# LKS_EVB_MCU081_V2_0.net
KiCad netlist of a schematic drawn in Altium Designer
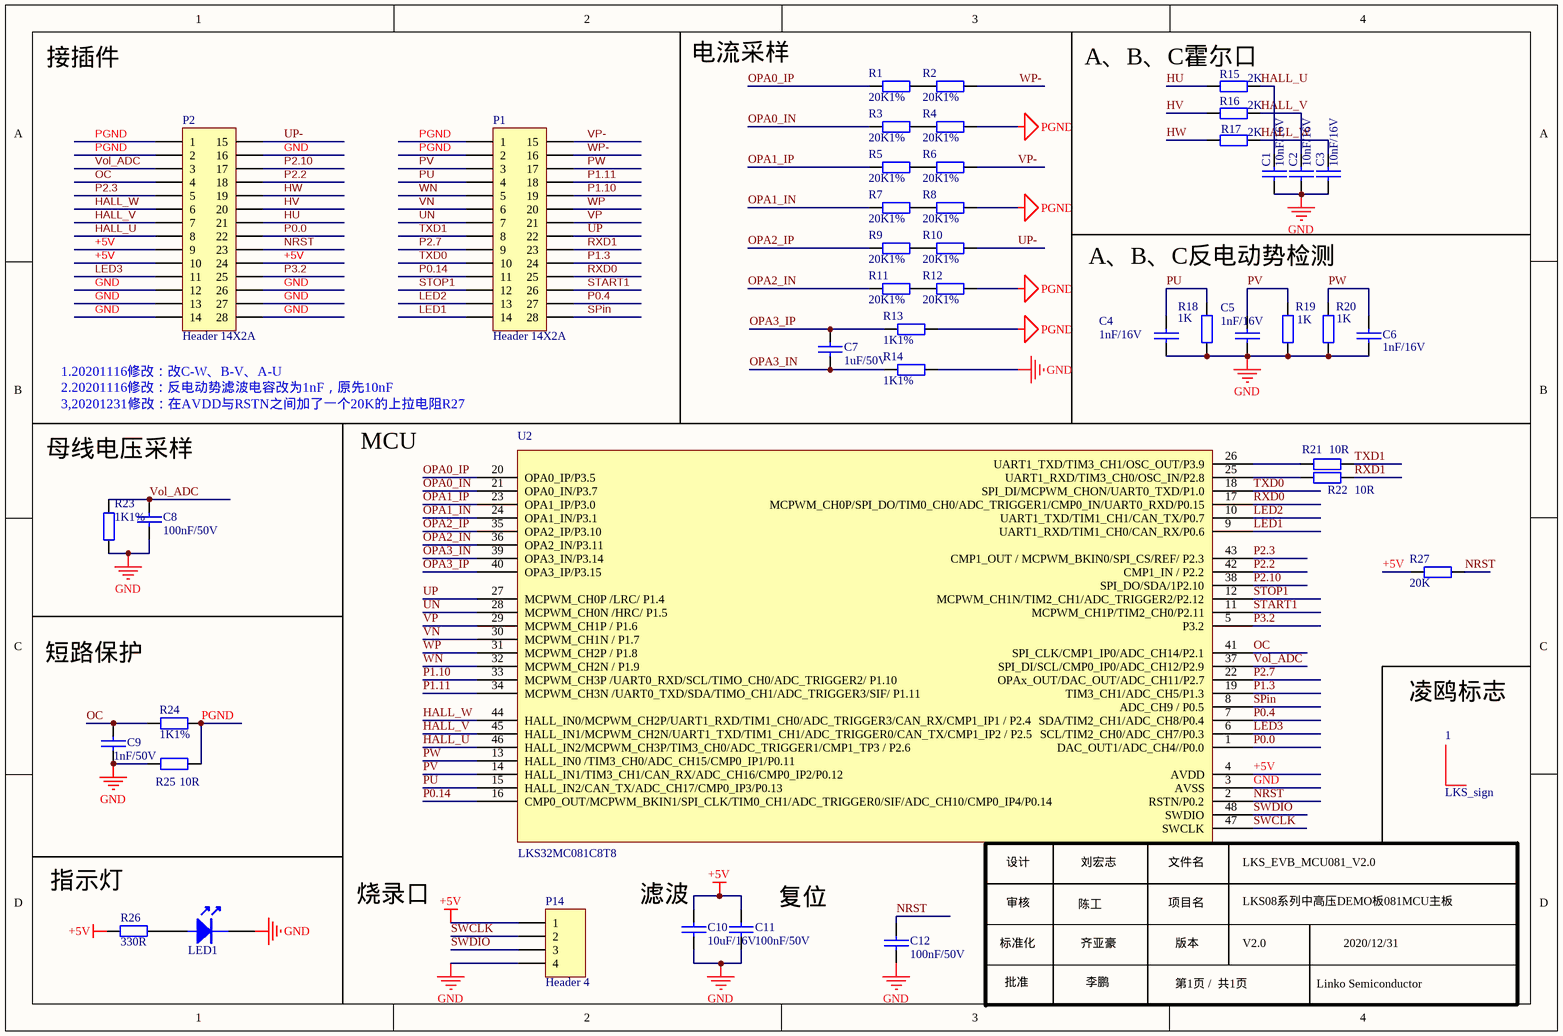
[diagram p0: LKS_EVB_MCU081_V2.0.SchDoc]

(export (version "E")
  (design (tool "Eeschema 10.0.6"))
  (components
    (comp (ref "1")
      (value "LKS_sign")
      (footprint "LKS_LOGO2")
      (libsource (lib "linko sch library") (part "LKS_sign"))
    )
    (comp (ref "C1")
      (value "10nF/16V")
      (footprint "0603C")
      (description "Capacitor")
      (libsource (lib "*") (part "CAP"))
    )
    (comp (ref "C2")
      (value "10nF/16V")
      (footprint "0603C")
      (description "Capacitor")
      (libsource (lib "*") (part "CAP"))
    )
    (comp (ref "C3")
      (value "10nF/16V")
      (footprint "0603C")
      (description "Capacitor")
      (libsource (lib "*") (part "CAP"))
    )
    (comp (ref "C4")
      (value "1nF/16V")
      (footprint "0603C")
      (description "Capacitor")
      (libsource (lib "*") (part "CAP"))
    )
    (comp (ref "C5")
      (value "1nF/16V")
      (footprint "0603C")
      (description "Capacitor")
      (libsource (lib "*") (part "CAP"))
    )
    (comp (ref "C6")
      (value "1nF/16V")
      (footprint "0603C")
      (description "Capacitor")
      (libsource (lib "*") (part "CAP"))
    )
    (comp (ref "C7")
      (value "1uF/50V")
      (footprint "0603C")
      (description "Capacitor")
      (libsource (lib "*") (part "C"))
    )
    (comp (ref "C8")
      (value "100nF/50V")
      (footprint "0603C")
      (description "Capacitor")
      (libsource (lib "*") (part "C"))
    )
    (comp (ref "C9")
      (value "1nF/50V")
      (footprint "0603C")
      (description "Capacitor")
      (libsource (lib "*") (part "C"))
    )
    (comp (ref "C10")
      (value "10uF/16V")
      (footprint "0603C")
      (description "Capacitor")
      (libsource (lib "*") (part "C"))
    )
    (comp (ref "C11")
      (value "100nF/50V")
      (footprint "0603C")
      (description "Capacitor")
      (libsource (lib "*") (part "C"))
    )
    (comp (ref "C12")
      (value "100nF/50V")
      (footprint "0603C")
      (description "Capacitor")
      (libsource (lib "*") (part "C"))
    )
    (comp (ref "LED1")
      (value "LED")
      (footprint "LED 0603R")
      (description "LED_Light")
      (libsource (lib "LINKO_V1.0") (part "LED"))
    )
    (comp (ref "P1")
      (value "Header 14X2A")
      (footprint "HDR2X14_CEN")
      (description "Header, 14-Pin, Dual row")
      (fields (field (name "PUBLISHER") "Altium Limited"))
      (libsource (lib "Miscellaneous Connectors") (part "Header 14X2A"))
    )
    (comp (ref "P2")
      (value "Header 14X2A")
      (footprint "HDR2X14_CEN")
      (description "Header, 14-Pin, Dual row")
      (fields (field (name "PUBLISHER") "Altium Limited"))
      (libsource (lib "Miscellaneous Connectors") (part "Header 14X2A"))
    )
    (comp (ref "P14")
      (value "Header 4")
      (footprint "HDR1X4")
      (description "Header, 4-Pin")
      (fields (field (name "PUBLISHER") "Altium Limited"))
      (libsource (lib "Miscellaneous Connectors") (part "Header 4"))
    )
    (comp (ref "R1")
      (value "20K1%")
      (footprint "0603R")
      (description "Resistor")
      (fields (field (name "PUBLISHER") "Altium Limited"))
      (libsource (lib "LINKO_V1.0") (part "Res"))
    )
    (comp (ref "R2")
      (value "20K1%")
      (footprint "0603R")
      (description "Resistor")
      (fields (field (name "PUBLISHER") "Altium Limited"))
      (libsource (lib "LINKO_V1.0") (part "Res"))
    )
    (comp (ref "R3")
      (value "20K1%")
      (footprint "0603R")
      (description "Resistor")
      (fields (field (name "PUBLISHER") "Altium Limited"))
      (libsource (lib "LINKO_V1.0") (part "Res"))
    )
    (comp (ref "R4")
      (value "20K1%")
      (footprint "0603R")
      (description "Resistor")
      (fields (field (name "PUBLISHER") "Altium Limited"))
      (libsource (lib "LINKO_V1.0") (part "Res"))
    )
    (comp (ref "R5")
      (value "20K1%")
      (footprint "0603R")
      (description "Resistor")
      (fields (field (name "PUBLISHER") "Altium Limited"))
      (libsource (lib "LINKO_V1.0") (part "Res"))
    )
    (comp (ref "R6")
      (value "20K1%")
      (footprint "0603R")
      (description "Resistor")
      (fields (field (name "PUBLISHER") "Altium Limited"))
      (libsource (lib "LINKO_V1.0") (part "Res"))
    )
    (comp (ref "R7")
      (value "20K1%")
      (footprint "0603R")
      (description "Resistor")
      (fields (field (name "PUBLISHER") "Altium Limited"))
      (libsource (lib "LINKO_V1.0") (part "Res"))
    )
    (comp (ref "R8")
      (value "20K1%")
      (footprint "0603R")
      (description "Resistor")
      (fields (field (name "PUBLISHER") "Altium Limited"))
      (libsource (lib "LINKO_V1.0") (part "Res"))
    )
    (comp (ref "R9")
      (value "20K1%")
      (footprint "0603R")
      (description "Resistor")
      (fields (field (name "PUBLISHER") "Altium Limited"))
      (libsource (lib "LINKO_V1.0") (part "Res"))
    )
    (comp (ref "R10")
      (value "20K1%")
      (footprint "0603R")
      (description "Resistor")
      (fields (field (name "PUBLISHER") "Altium Limited"))
      (libsource (lib "LINKO_V1.0") (part "Res"))
    )
    (comp (ref "R11")
      (value "20K1%")
      (footprint "0603R")
      (description "Resistor")
      (fields (field (name "PUBLISHER") "Altium Limited"))
      (libsource (lib "LINKO_V1.0") (part "Res"))
    )
    (comp (ref "R12")
      (value "20K1%")
      (footprint "0603R")
      (description "Resistor")
      (fields (field (name "PUBLISHER") "Altium Limited"))
      (libsource (lib "LINKO_V1.0") (part "Res"))
    )
    (comp (ref "R13")
      (value "1K1%")
      (footprint "0603R")
      (description "Resistor")
      (fields (field (name "PUBLISHER") "Altium Limited"))
      (libsource (lib "LINKO_V1.0") (part "Res"))
    )
    (comp (ref "R14")
      (value "1K1%")
      (footprint "0603R")
      (description "Resistor")
      (fields (field (name "PUBLISHER") "Altium Limited"))
      (libsource (lib "LINKO_V1.0") (part "Res"))
    )
    (comp (ref "R15")
      (value "2K")
      (footprint "0603R")
      (description "Resistor")
      (fields (field (name "PUBLISHER") "Altium Limited"))
      (libsource (lib "") (part "Res_2"))
    )
    (comp (ref "R16")
      (value "2K")
      (footprint "0603R")
      (description "Resistor")
      (fields (field (name "PUBLISHER") "Altium Limited"))
      (libsource (lib "") (part "Res_2"))
    )
    (comp (ref "R17")
      (value "2K")
      (footprint "0603R")
      (description "Resistor")
      (fields (field (name "PUBLISHER") "Altium Limited"))
      (libsource (lib "") (part "Res_2"))
    )
    (comp (ref "R18")
      (value "1K")
      (footprint "0603R")
      (description "Resistor")
      (fields (field (name "PUBLISHER") "Altium Limited"))
      (libsource (lib "LINKO_V1.0") (part "Res"))
    )
    (comp (ref "R19")
      (value "1K")
      (footprint "0603R")
      (description "Resistor")
      (fields (field (name "PUBLISHER") "Altium Limited"))
      (libsource (lib "LINKO_V1.0") (part "Res"))
    )
    (comp (ref "R20")
      (value "1K")
      (footprint "0603R")
      (description "Resistor")
      (fields (field (name "PUBLISHER") "Altium Limited"))
      (libsource (lib "LINKO_V1.0") (part "Res"))
    )
    (comp (ref "R21")
      (value "10R")
      (footprint "0603R")
      (description "Resistor")
      (fields (field (name "PUBLISHER") "Altium Limited"))
      (libsource (lib "") (part "Res_3"))
    )
    (comp (ref "R22")
      (value "10R")
      (footprint "0603R")
      (description "Resistor")
      (fields (field (name "PUBLISHER") "Altium Limited"))
      (libsource (lib "") (part "Res_1"))
    )
    (comp (ref "R23")
      (value "1K1%")
      (footprint "0603R")
      (description "Resistor")
      (fields (field (name "PUBLISHER") "Altium Limited"))
      (libsource (lib "") (part "Res_1"))
    )
    (comp (ref "R24")
      (value "1K1%")
      (footprint "0603R")
      (description "Resistor")
      (fields (field (name "PUBLISHER") "Altium Limited"))
      (libsource (lib "") (part "Res_2"))
    )
    (comp (ref "R25")
      (value "10R")
      (footprint "0603R")
      (description "Resistor")
      (fields (field (name "PUBLISHER") "Altium Limited"))
      (libsource (lib "LINKO_V1.0") (part "Res"))
    )
    (comp (ref "R26")
      (value "330R")
      (footprint "0603R")
      (description "Resistor")
      (fields (field (name "PUBLISHER") "Altium Limited"))
      (libsource (lib "") (part "Res_1"))
    )
    (comp (ref "R27")
      (value "20K")
      (footprint "0603R")
      (description "Resistor")
      (fields (field (name "PUBLISHER") "Altium Limited"))
      (libsource (lib "LINKO_V1.0") (part "Res"))
    )
    (comp (ref "U2")
      (value "LKS32MC081C8T8")
      (footprint "LINKO-081")
      (description "芯片")
      (libsource (lib "LINKO_V1.0") (part "LKS081C8T8"))
    )
  )
  (nets
    (net (code "1") (name "+5V") (class "Default")
      (node (ref "C10") (pin "2") (pinfunction "2_2") (pintype "passive"))
      (node (ref "C11") (pin "2") (pinfunction "2_2") (pintype "passive"))
      (node (ref "P14") (pin "1") (pinfunction "1_1") (pintype "passive"))
      (node (ref "P2") (pin "10") (pinfunction "10_10") (pintype "passive"))
      (node (ref "P2") (pin "24") (pinfunction "24_24") (pintype "passive"))
      (node (ref "P2") (pin "9") (pinfunction "9_9") (pintype "passive"))
      (node (ref "R26") (pin "1") (pinfunction "1_1") (pintype "passive"))
      (node (ref "R27") (pin "2") (pinfunction "2_2") (pintype "passive"))
      (node (ref "U2") (pin "4") (pinfunction "AVDD_4") (pintype "passive"))
    )
    (net (code "2") (name "/HALL_U") (class "Default")
      (node (ref "C1") (pin "1") (pinfunction "1_1") (pintype "passive"))
      (node (ref "P2") (pin "8") (pinfunction "8_8") (pintype "passive"))
      (node (ref "R15") (pin "2") (pinfunction "2_2") (pintype "passive"))
      (node (ref "U2") (pin "46") (pinfunction "HALL_IN2/MCPWM_CH3P/TIM3_CH0/ADC_TRIGGER1/CMP1_TP3_/_P2.6_46") (pintype "passive"))
    )
    (net (code "3") (name "/HALL_V") (class "Default")
      (node (ref "C2") (pin "1") (pinfunction "1_1") (pintype "passive"))
      (node (ref "P2") (pin "7") (pinfunction "7_7") (pintype "passive"))
      (node (ref "R16") (pin "2") (pinfunction "2_2") (pintype "passive"))
      (node (ref "U2") (pin "45") (pinfunction "HALL_IN1/MCPWM_CH2N/UART1_TXD/TIM1_CH1/ADC_TRIGGER0/CAN_TX/CMP1_IP2_/_P2.5_45") (pintype "passive"))
    )
    (net (code "4") (name "/HALL_W") (class "Default")
      (node (ref "C3") (pin "1") (pinfunction "1_1") (pintype "passive"))
      (node (ref "P2") (pin "6") (pinfunction "6_6") (pintype "passive"))
      (node (ref "R17") (pin "2") (pinfunction "2_2") (pintype "passive"))
      (node (ref "U2") (pin "44") (pinfunction "HALL_IN0/MCPWM_CH2P/UART1_RXD/TIM1_CH0/ADC_TRIGGER3/CAN_RX/CMP1_IP1_/_P2.4_44") (pintype "passive"))
    )
    (net (code "5") (name "/HU") (class "Default")
      (node (ref "P2") (pin "21") (pinfunction "21_21") (pintype "passive"))
      (node (ref "R15") (pin "1") (pinfunction "1_1") (pintype "passive"))
    )
    (net (code "6") (name "/HV") (class "Default")
      (node (ref "P2") (pin "20") (pinfunction "20_20") (pintype "passive"))
      (node (ref "R16") (pin "1") (pinfunction "1_1") (pintype "passive"))
    )
    (net (code "7") (name "/HW") (class "Default")
      (node (ref "P2") (pin "19") (pinfunction "19_19") (pintype "passive"))
      (node (ref "R17") (pin "1") (pinfunction "1_1") (pintype "passive"))
    )
    (net (code "8") (name "/LED1") (class "Default")
      (node (ref "P1") (pin "14") (pinfunction "14_14") (pintype "passive"))
      (node (ref "U2") (pin "9") (pinfunction "UART1_RXD/TIM1_CH0/CAN_RX/P0.6_9") (pintype "passive"))
    )
    (net (code "9") (name "/LED2") (class "Default")
      (node (ref "P1") (pin "13") (pinfunction "13_13") (pintype "passive"))
      (node (ref "U2") (pin "10") (pinfunction "UART1_TXD/TIM1_CH1/CAN_TX/P0.7_10") (pintype "passive"))
    )
    (net (code "10") (name "/LED3") (class "Default")
      (node (ref "P2") (pin "11") (pinfunction "11_11") (pintype "passive"))
      (node (ref "U2") (pin "6") (pinfunction "SCL/TIM2_CH0/ADC_CH7/P0.3_6") (pintype "passive"))
    )
    (net (code "11") (name "/NRST") (class "Default")
      (node (ref "C12") (pin "1") (pinfunction "1_1") (pintype "passive"))
      (node (ref "P2") (pin "23") (pinfunction "23_23") (pintype "passive"))
      (node (ref "R27") (pin "1") (pinfunction "1_1") (pintype "passive"))
      (node (ref "U2") (pin "2") (pinfunction "RSTN/P0.2_2") (pintype "passive"))
    )
    (net (code "12") (name "/OC") (class "Default")
      (node (ref "C9") (pin "2") (pinfunction "2_2") (pintype "passive"))
      (node (ref "P2") (pin "4") (pinfunction "4_4") (pintype "passive"))
      (node (ref "R24") (pin "1") (pinfunction "1_1") (pintype "passive"))
      (node (ref "U2") (pin "41") (pinfunction "SPI_CLK/CMP1_IP0/ADC_CH14/P2.1_41") (pintype "passive"))
    )
    (net (code "13") (name "/OPA0_IN") (class "Default")
      (node (ref "R3") (pin "2") (pinfunction "2_2") (pintype "passive"))
      (node (ref "U2") (pin "21") (pinfunction "OPA0_IN/P3.7_21") (pintype "passive"))
    )
    (net (code "14") (name "/OPA0_IP") (class "Default")
      (node (ref "R1") (pin "2") (pinfunction "2_2") (pintype "passive"))
      (node (ref "U2") (pin "20") (pinfunction "OPA0_IP/P3.5_20") (pintype "passive"))
    )
    (net (code "15") (name "/OPA1_IN") (class "Default")
      (node (ref "R7") (pin "2") (pinfunction "2_2") (pintype "passive"))
      (node (ref "U2") (pin "24") (pinfunction "OPA1_IN/P3.1_24") (pintype "passive"))
    )
    (net (code "16") (name "/OPA1_IP") (class "Default")
      (node (ref "R5") (pin "2") (pinfunction "2_2") (pintype "passive"))
      (node (ref "U2") (pin "23") (pinfunction "OPA1_IP/P3.0_23") (pintype "passive"))
    )
    (net (code "17") (name "/OPA2_IN") (class "Default")
      (node (ref "R11") (pin "2") (pinfunction "2_2") (pintype "passive"))
      (node (ref "U2") (pin "36") (pinfunction "OPA2_IN/P3.11_36") (pintype "passive"))
    )
    (net (code "18") (name "/OPA2_IP") (class "Default")
      (node (ref "R9") (pin "2") (pinfunction "2_2") (pintype "passive"))
      (node (ref "U2") (pin "35") (pinfunction "OPA2_IP/P3.10_35") (pintype "passive"))
    )
    (net (code "19") (name "/OPA3_IN") (class "Default")
      (node (ref "C7") (pin "2") (pinfunction "2_2") (pintype "passive"))
      (node (ref "R14") (pin "2") (pinfunction "2_2") (pintype "passive"))
      (node (ref "U2") (pin "39") (pinfunction "OPA3_IN/P3.14_39") (pintype "passive"))
    )
    (net (code "20") (name "/OPA3_IP") (class "Default")
      (node (ref "C7") (pin "1") (pinfunction "1_1") (pintype "passive"))
      (node (ref "R13") (pin "2") (pinfunction "2_2") (pintype "passive"))
      (node (ref "U2") (pin "40") (pinfunction "OPA3_IP/P3.15_40") (pintype "passive"))
    )
    (net (code "21") (name "/P0.0") (class "Default")
      (node (ref "P2") (pin "22") (pinfunction "22_22") (pintype "passive"))
      (node (ref "U2") (pin "1") (pinfunction "DAC_OUT1/ADC_CH4//P0.0_1") (pintype "passive"))
    )
    (net (code "22") (name "/P0.4") (class "Default")
      (node (ref "P1") (pin "27") (pinfunction "27_27") (pintype "passive"))
      (node (ref "U2") (pin "7") (pinfunction "SDA/TIM2_CH1/ADC_CH8/P0.4_7") (pintype "passive"))
    )
    (net (code "23") (name "/P0.14") (class "Default")
      (node (ref "P1") (pin "11") (pinfunction "11_11") (pintype "passive"))
      (node (ref "U2") (pin "16") (pinfunction "CMP0_OUT/MCPWM_BKIN1/SPI_CLK/TIM0_CH1/ADC_TRIGGER0/SIF/ADC_CH10/CMP0_IP4/P0.14_16") (pintype "passive"))
    )
    (net (code "24") (name "/P1.3") (class "Default")
      (node (ref "P1") (pin "24") (pinfunction "24_24") (pintype "passive"))
      (node (ref "U2") (pin "19") (pinfunction "TIM3_CH1/ADC_CH5/P1.3_19") (pintype "passive"))
    )
    (net (code "25") (name "/P1.10") (class "Default")
      (node (ref "P1") (pin "19") (pinfunction "19_19") (pintype "passive"))
      (node (ref "U2") (pin "33") (pinfunction "MCPWM_CH3P_/UART0_RXD/SCL/TIMO_CH0/ADC_TRIGGER2/_P1.10_33") (pintype "passive"))
    )
    (net (code "26") (name "/P1.11") (class "Default")
      (node (ref "P1") (pin "18") (pinfunction "18_18") (pintype "passive"))
      (node (ref "U2") (pin "34") (pinfunction "MCPWM_CH3N_/UART0_TXD/SDA/TIMO_CH1/ADC_TRIGGER3/SIF/_P1.11_34") (pintype "passive"))
    )
    (net (code "27") (name "/P2.2") (class "Default")
      (node (ref "P2") (pin "18") (pinfunction "18_18") (pintype "passive"))
      (node (ref "U2") (pin "42") (pinfunction "CMP1_IN_/_P2.2_42") (pintype "passive"))
    )
    (net (code "28") (name "/P2.3") (class "Default")
      (node (ref "P2") (pin "5") (pinfunction "5_5") (pintype "passive"))
      (node (ref "U2") (pin "43") (pinfunction "CMP1_OUT_/_MCPWM_BKIN0/SPI_CS/REF/_P2.3_43") (pintype "passive"))
    )
    (net (code "29") (name "/P2.7") (class "Default")
      (node (ref "P1") (pin "9") (pinfunction "9_9") (pintype "passive"))
      (node (ref "U2") (pin "22") (pinfunction "OPAx_OUT/DAC_OUT/ADC_CH11/P2.7_22") (pintype "passive"))
    )
    (net (code "30") (name "/P2.10") (class "Default")
      (node (ref "P2") (pin "17") (pinfunction "17_17") (pintype "passive"))
      (node (ref "U2") (pin "38") (pinfunction "SPI_DO/SDA/1P2.10_38") (pintype "passive"))
    )
    (net (code "31") (name "/P3.2") (class "Default")
      (node (ref "P2") (pin "25") (pinfunction "25_25") (pintype "passive"))
      (node (ref "U2") (pin "5") (pinfunction "P3.2_5") (pintype "passive"))
    )
    (net (code "32") (name "/PU") (class "Default")
      (node (ref "C4") (pin "1") (pinfunction "1_1") (pintype "passive"))
      (node (ref "P1") (pin "4") (pinfunction "4_4") (pintype "passive"))
      (node (ref "R18") (pin "1") (pinfunction "1_1") (pintype "passive"))
      (node (ref "U2") (pin "15") (pinfunction "HALL_IN2/CAN_TX/ADC_CH17/CMP0_IP3/P0.13_15") (pintype "passive"))
    )
    (net (code "33") (name "/PV") (class "Default")
      (node (ref "C5") (pin "1") (pinfunction "1_1") (pintype "passive"))
      (node (ref "P1") (pin "3") (pinfunction "3_3") (pintype "passive"))
      (node (ref "R19") (pin "1") (pinfunction "1_1") (pintype "passive"))
      (node (ref "U2") (pin "14") (pinfunction "HALL_IN1/TIM3_CH1/CAN_RX/ADC_CH16/CMP0_IP2/P0.12_14") (pintype "passive"))
    )
    (net (code "34") (name "/PW") (class "Default")
      (node (ref "C6") (pin "1") (pinfunction "1_1") (pintype "passive"))
      (node (ref "P1") (pin "17") (pinfunction "17_17") (pintype "passive"))
      (node (ref "R20") (pin "1") (pinfunction "1_1") (pintype "passive"))
      (node (ref "U2") (pin "13") (pinfunction "HALL_IN0_/TIM3_CH0/ADC_CH15/CMP0_IP1/P0.11_13") (pintype "passive"))
    )
    (net (code "35") (name "/RXD0") (class "Default")
      (node (ref "P1") (pin "25") (pinfunction "25_25") (pintype "passive"))
      (node (ref "U2") (pin "17") (pinfunction "MCPWM_CH0P/SPI_DO/TIM0_CH0/ADC_TRIGGER1/CMP0_IN/UART0_RXD/P0.15_17") (pintype "passive"))
    )
    (net (code "36") (name "/RXD1") (class "Default")
      (node (ref "P1") (pin "23") (pinfunction "23_23") (pintype "passive"))
      (node (ref "R22") (pin "2") (pinfunction "2_2") (pintype "passive"))
    )
    (net (code "37") (name "/SPin") (class "Default")
      (node (ref "P1") (pin "28") (pinfunction "28_28") (pintype "passive"))
      (node (ref "U2") (pin "8") (pinfunction "ADC_CH9_/_P0.5_8") (pintype "passive"))
    )
    (net (code "38") (name "/START1") (class "Default")
      (node (ref "P1") (pin "26") (pinfunction "26_26") (pintype "passive"))
      (node (ref "U2") (pin "11") (pinfunction "MCPWM_CH1P/TIM2_CH0/P2.11_11") (pintype "passive"))
    )
    (net (code "39") (name "/STOP1") (class "Default")
      (node (ref "P1") (pin "12") (pinfunction "12_12") (pintype "passive"))
      (node (ref "U2") (pin "12") (pinfunction "MCPWM_CH1N/TIM2_CH1/ADC_TRIGGER2/P2.12_12") (pintype "passive"))
    )
    (net (code "40") (name "/SWCLK") (class "Default")
      (node (ref "P14") (pin "2") (pinfunction "2_2") (pintype "passive"))
      (node (ref "U2") (pin "47") (pinfunction "SWCLK_47") (pintype "passive"))
    )
    (net (code "41") (name "/SWDIO") (class "Default")
      (node (ref "P14") (pin "3") (pinfunction "3_3") (pintype "passive"))
      (node (ref "U2") (pin "48") (pinfunction "SWDIO_48") (pintype "passive"))
    )
    (net (code "42") (name "/TXD0") (class "Default")
      (node (ref "P1") (pin "10") (pinfunction "10_10") (pintype "passive"))
      (node (ref "U2") (pin "18") (pinfunction "SPI_DI/MCPWM_CHON/UART0_TXD/P1.0_18") (pintype "passive"))
    )
    (net (code "43") (name "/TXD1") (class "Default")
      (node (ref "P1") (pin "8") (pinfunction "8_8") (pintype "passive"))
      (node (ref "R21") (pin "1") (pinfunction "1_1") (pintype "passive"))
    )
    (net (code "44") (name "/UN") (class "Default")
      (node (ref "P1") (pin "7") (pinfunction "7_7") (pintype "passive"))
      (node (ref "U2") (pin "28") (pinfunction "MCPWM_CH0N_/HRC/_P1.5_28") (pintype "passive"))
    )
    (net (code "45") (name "/UP") (class "Default")
      (node (ref "P1") (pin "22") (pinfunction "22_22") (pintype "passive"))
      (node (ref "U2") (pin "27") (pinfunction "MCPWM_CH0P_/LRC/_P1.4_27") (pintype "passive"))
    )
    (net (code "46") (name "/UP-") (class "Default")
      (node (ref "P2") (pin "15") (pinfunction "15_15") (pintype "passive"))
      (node (ref "R10") (pin "1") (pinfunction "1_1") (pintype "passive"))
    )
    (net (code "47") (name "/VN") (class "Default")
      (node (ref "P1") (pin "6") (pinfunction "6_6") (pintype "passive"))
      (node (ref "U2") (pin "30") (pinfunction "MCPWM_CH1N_/_P1.7_30") (pintype "passive"))
    )
    (net (code "48") (name "/VP") (class "Default")
      (node (ref "P1") (pin "21") (pinfunction "21_21") (pintype "passive"))
      (node (ref "U2") (pin "29") (pinfunction "MCPWM_CH1P_/_P1.6_29") (pintype "passive"))
    )
    (net (code "49") (name "/VP-") (class "Default")
      (node (ref "P1") (pin "15") (pinfunction "15_15") (pintype "passive"))
      (node (ref "R6") (pin "1") (pinfunction "1_1") (pintype "passive"))
    )
    (net (code "50") (name "/Vol_ADC") (class "Default")
      (node (ref "C8") (pin "2") (pinfunction "2_2") (pintype "passive"))
      (node (ref "P2") (pin "3") (pinfunction "3_3") (pintype "passive"))
      (node (ref "R23") (pin "2") (pinfunction "2_2") (pintype "passive"))
      (node (ref "U2") (pin "37") (pinfunction "SPI_DI/SCL/CMP0_IP0/ADC_CH12/P2.9_37") (pintype "passive"))
    )
    (net (code "51") (name "/WN") (class "Default")
      (node (ref "P1") (pin "5") (pinfunction "5_5") (pintype "passive"))
      (node (ref "U2") (pin "32") (pinfunction "MCPWM_CH2N_/_P1.9_32") (pintype "passive"))
    )
    (net (code "52") (name "/WP") (class "Default")
      (node (ref "P1") (pin "20") (pinfunction "20_20") (pintype "passive"))
      (node (ref "U2") (pin "31") (pinfunction "MCPWM_CH2P_/_P1.8_31") (pintype "passive"))
    )
    (net (code "53") (name "/WP-") (class "Default")
      (node (ref "P1") (pin "16") (pinfunction "16_16") (pintype "passive"))
      (node (ref "R2") (pin "1") (pinfunction "1_1") (pintype "passive"))
    )
    (net (code "54") (name "GND") (class "Default")
      (node (ref "C1") (pin "2") (pinfunction "2_2") (pintype "passive"))
      (node (ref "C10") (pin "1") (pinfunction "1_1") (pintype "passive"))
      (node (ref "C11") (pin "1") (pinfunction "1_1") (pintype "passive"))
      (node (ref "C12") (pin "2") (pinfunction "2_2") (pintype "passive"))
      (node (ref "C2") (pin "2") (pinfunction "2_2") (pintype "passive"))
      (node (ref "C3") (pin "2") (pinfunction "2_2") (pintype "passive"))
      (node (ref "C4") (pin "2") (pinfunction "2_2") (pintype "passive"))
      (node (ref "C5") (pin "2") (pinfunction "2_2") (pintype "passive"))
      (node (ref "C6") (pin "2") (pinfunction "2_2") (pintype "passive"))
      (node (ref "C8") (pin "1") (pinfunction "1_1") (pintype "passive"))
      (node (ref "C9") (pin "1") (pinfunction "1_1") (pintype "passive"))
      (node (ref "LED1") (pin "2") (pinfunction "K_2") (pintype "passive"))
      (node (ref "P14") (pin "4") (pinfunction "4_4") (pintype "passive"))
      (node (ref "P2") (pin "12") (pinfunction "12_12") (pintype "passive"))
      (node (ref "P2") (pin "13") (pinfunction "13_13") (pintype "passive"))
      (node (ref "P2") (pin "14") (pinfunction "14_14") (pintype "passive"))
      (node (ref "P2") (pin "16") (pinfunction "16_16") (pintype "passive"))
      (node (ref "P2") (pin "26") (pinfunction "26_26") (pintype "passive"))
      (node (ref "P2") (pin "27") (pinfunction "27_27") (pintype "passive"))
      (node (ref "P2") (pin "28") (pinfunction "28_28") (pintype "passive"))
      (node (ref "R14") (pin "1") (pinfunction "1_1") (pintype "passive"))
      (node (ref "R18") (pin "2") (pinfunction "2_2") (pintype "passive"))
      (node (ref "R19") (pin "2") (pinfunction "2_2") (pintype "passive"))
      (node (ref "R20") (pin "2") (pinfunction "2_2") (pintype "passive"))
      (node (ref "R23") (pin "1") (pinfunction "1_1") (pintype "passive"))
      (node (ref "R25") (pin "2") (pinfunction "2_2") (pintype "passive"))
      (node (ref "U2") (pin "3") (pinfunction "AVSS_3") (pintype "passive"))
    )
    (net (code "55") (name "Net-(LED1-A)") (class "Default")
      (node (ref "LED1") (pin "1") (pinfunction "A_1") (pintype "passive"))
      (node (ref "R26") (pin "2") (pinfunction "2_2") (pintype "passive"))
    )
    (net (code "56") (name "Net-(R1-Pad1)") (class "Default")
      (node (ref "R1") (pin "1") (pinfunction "1_1") (pintype "passive"))
      (node (ref "R2") (pin "2") (pinfunction "2_2") (pintype "passive"))
    )
    (net (code "57") (name "Net-(R3-Pad1)") (class "Default")
      (node (ref "R3") (pin "1") (pinfunction "1_1") (pintype "passive"))
      (node (ref "R4") (pin "2") (pinfunction "2_2") (pintype "passive"))
    )
    (net (code "58") (name "Net-(R5-Pad1)") (class "Default")
      (node (ref "R5") (pin "1") (pinfunction "1_1") (pintype "passive"))
      (node (ref "R6") (pin "2") (pinfunction "2_2") (pintype "passive"))
    )
    (net (code "59") (name "Net-(R7-Pad1)") (class "Default")
      (node (ref "R7") (pin "1") (pinfunction "1_1") (pintype "passive"))
      (node (ref "R8") (pin "2") (pinfunction "2_2") (pintype "passive"))
    )
    (net (code "60") (name "Net-(R10-Pad2)") (class "Default")
      (node (ref "R10") (pin "2") (pinfunction "2_2") (pintype "passive"))
      (node (ref "R9") (pin "1") (pinfunction "1_1") (pintype "passive"))
    )
    (net (code "61") (name "Net-(R11-Pad1)") (class "Default")
      (node (ref "R11") (pin "1") (pinfunction "1_1") (pintype "passive"))
      (node (ref "R12") (pin "2") (pinfunction "2_2") (pintype "passive"))
    )
    (net (code "62") (name "Net-(U2-UART1_RXD{slash}TIM3_CH0{slash}OSC_IN{slash}P2.8)") (class "Default")
      (node (ref "R22") (pin "1") (pinfunction "1_1") (pintype "passive"))
      (node (ref "U2") (pin "25") (pinfunction "UART1_RXD/TIM3_CH0/OSC_IN/P2.8_25") (pintype "passive"))
    )
    (net (code "63") (name "Net-(U2-UART1_TXD{slash}TIM3_CH1{slash}OSC_OUT{slash}P3.9)") (class "Default")
      (node (ref "R21") (pin "2") (pinfunction "2_2") (pintype "passive"))
      (node (ref "U2") (pin "26") (pinfunction "UART1_TXD/TIM3_CH1/OSC_OUT/P3.9_26") (pintype "passive"))
    )
    (net (code "64") (name "PGND") (class "Default")
      (node (ref "P1") (pin "1") (pinfunction "1_1") (pintype "passive"))
      (node (ref "P1") (pin "2") (pinfunction "2_2") (pintype "passive"))
      (node (ref "P2") (pin "1") (pinfunction "1_1") (pintype "passive"))
      (node (ref "P2") (pin "2") (pinfunction "2_2") (pintype "passive"))
      (node (ref "R12") (pin "1") (pinfunction "1_1") (pintype "passive"))
      (node (ref "R13") (pin "1") (pinfunction "1_1") (pintype "passive"))
      (node (ref "R24") (pin "2") (pinfunction "2_2") (pintype "passive"))
      (node (ref "R25") (pin "1") (pinfunction "1_1") (pintype "passive"))
      (node (ref "R4") (pin "1") (pinfunction "1_1") (pintype "passive"))
      (node (ref "R8") (pin "1") (pinfunction "1_1") (pintype "passive"))
    )
  )
)
